# Power.net
KiCad netlist of a schematic drawn in Altium Designer
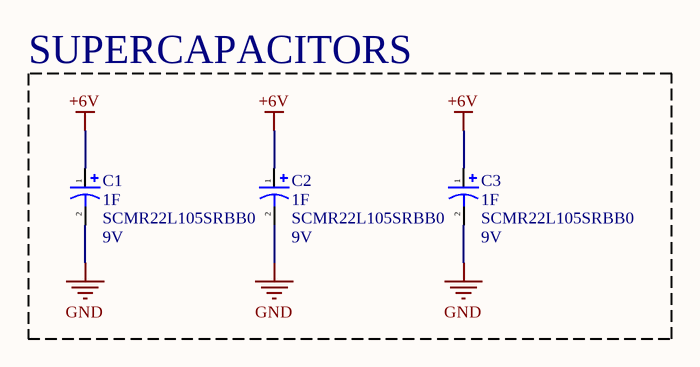
[diagram p0: Power.SchDoc]

(export (version "E")
  (design (tool "Eeschema 10.0.6"))
  (components
    (comp (ref "C1")
      (value "1F")
      (footprint "SCMR22L105SRBB0")
      (description "CAP 1F -10% +30% 9V T/H")
      (fields
        (field (name "MFR") "AVX Corporation")
        (field (name "TOLERANCE") "-10% +30%")
        (field (name "MANUFACTURER PART NUMBER") "SCMR22L105SRBB0")
        (field (name "RATED VOLTAGE") "9V")
      )
      (libsource (lib "CryptLib") (part "CAP_SCMR22L105SRBB0"))
    )
    (comp (ref "C2")
      (value "1F")
      (footprint "SCMR22L105SRBB0")
      (description "CAP 1F -10% +30% 9V T/H")
      (fields
        (field (name "MFR") "AVX Corporation")
        (field (name "TOLERANCE") "-10% +30%")
        (field (name "MANUFACTURER PART NUMBER") "SCMR22L105SRBB0")
        (field (name "RATED VOLTAGE") "9V")
      )
      (libsource (lib "CryptLib") (part "CAP_SCMR22L105SRBB0"))
    )
    (comp (ref "C3")
      (value "1F")
      (footprint "SCMR22L105SRBB0")
      (description "CAP 1F -10% +30% 9V T/H")
      (fields
        (field (name "MFR") "AVX Corporation")
        (field (name "TOLERANCE") "-10% +30%")
        (field (name "MANUFACTURER PART NUMBER") "SCMR22L105SRBB0")
        (field (name "RATED VOLTAGE") "9V")
      )
      (libsource (lib "CryptLib") (part "CAP_SCMR22L105SRBB0"))
    )
  )
  (nets
    (net (code "1") (name "+6V") (class "Default")
      (node (ref "C1") (pin "1") (pinfunction "1_1") (pintype "passive"))
      (node (ref "C2") (pin "1") (pinfunction "1_1") (pintype "passive"))
      (node (ref "C3") (pin "1") (pinfunction "1_1") (pintype "passive"))
    )
    (net (code "2") (name "GND") (class "Default")
      (node (ref "C1") (pin "2") (pinfunction "2_2") (pintype "passive"))
      (node (ref "C2") (pin "2") (pinfunction "2_2") (pintype "passive"))
      (node (ref "C3") (pin "2") (pinfunction "2_2") (pintype "passive"))
    )
  )
)
